# Box_Electronics_v26.net
KiCad netlist of a schematic drawn in EAGLE
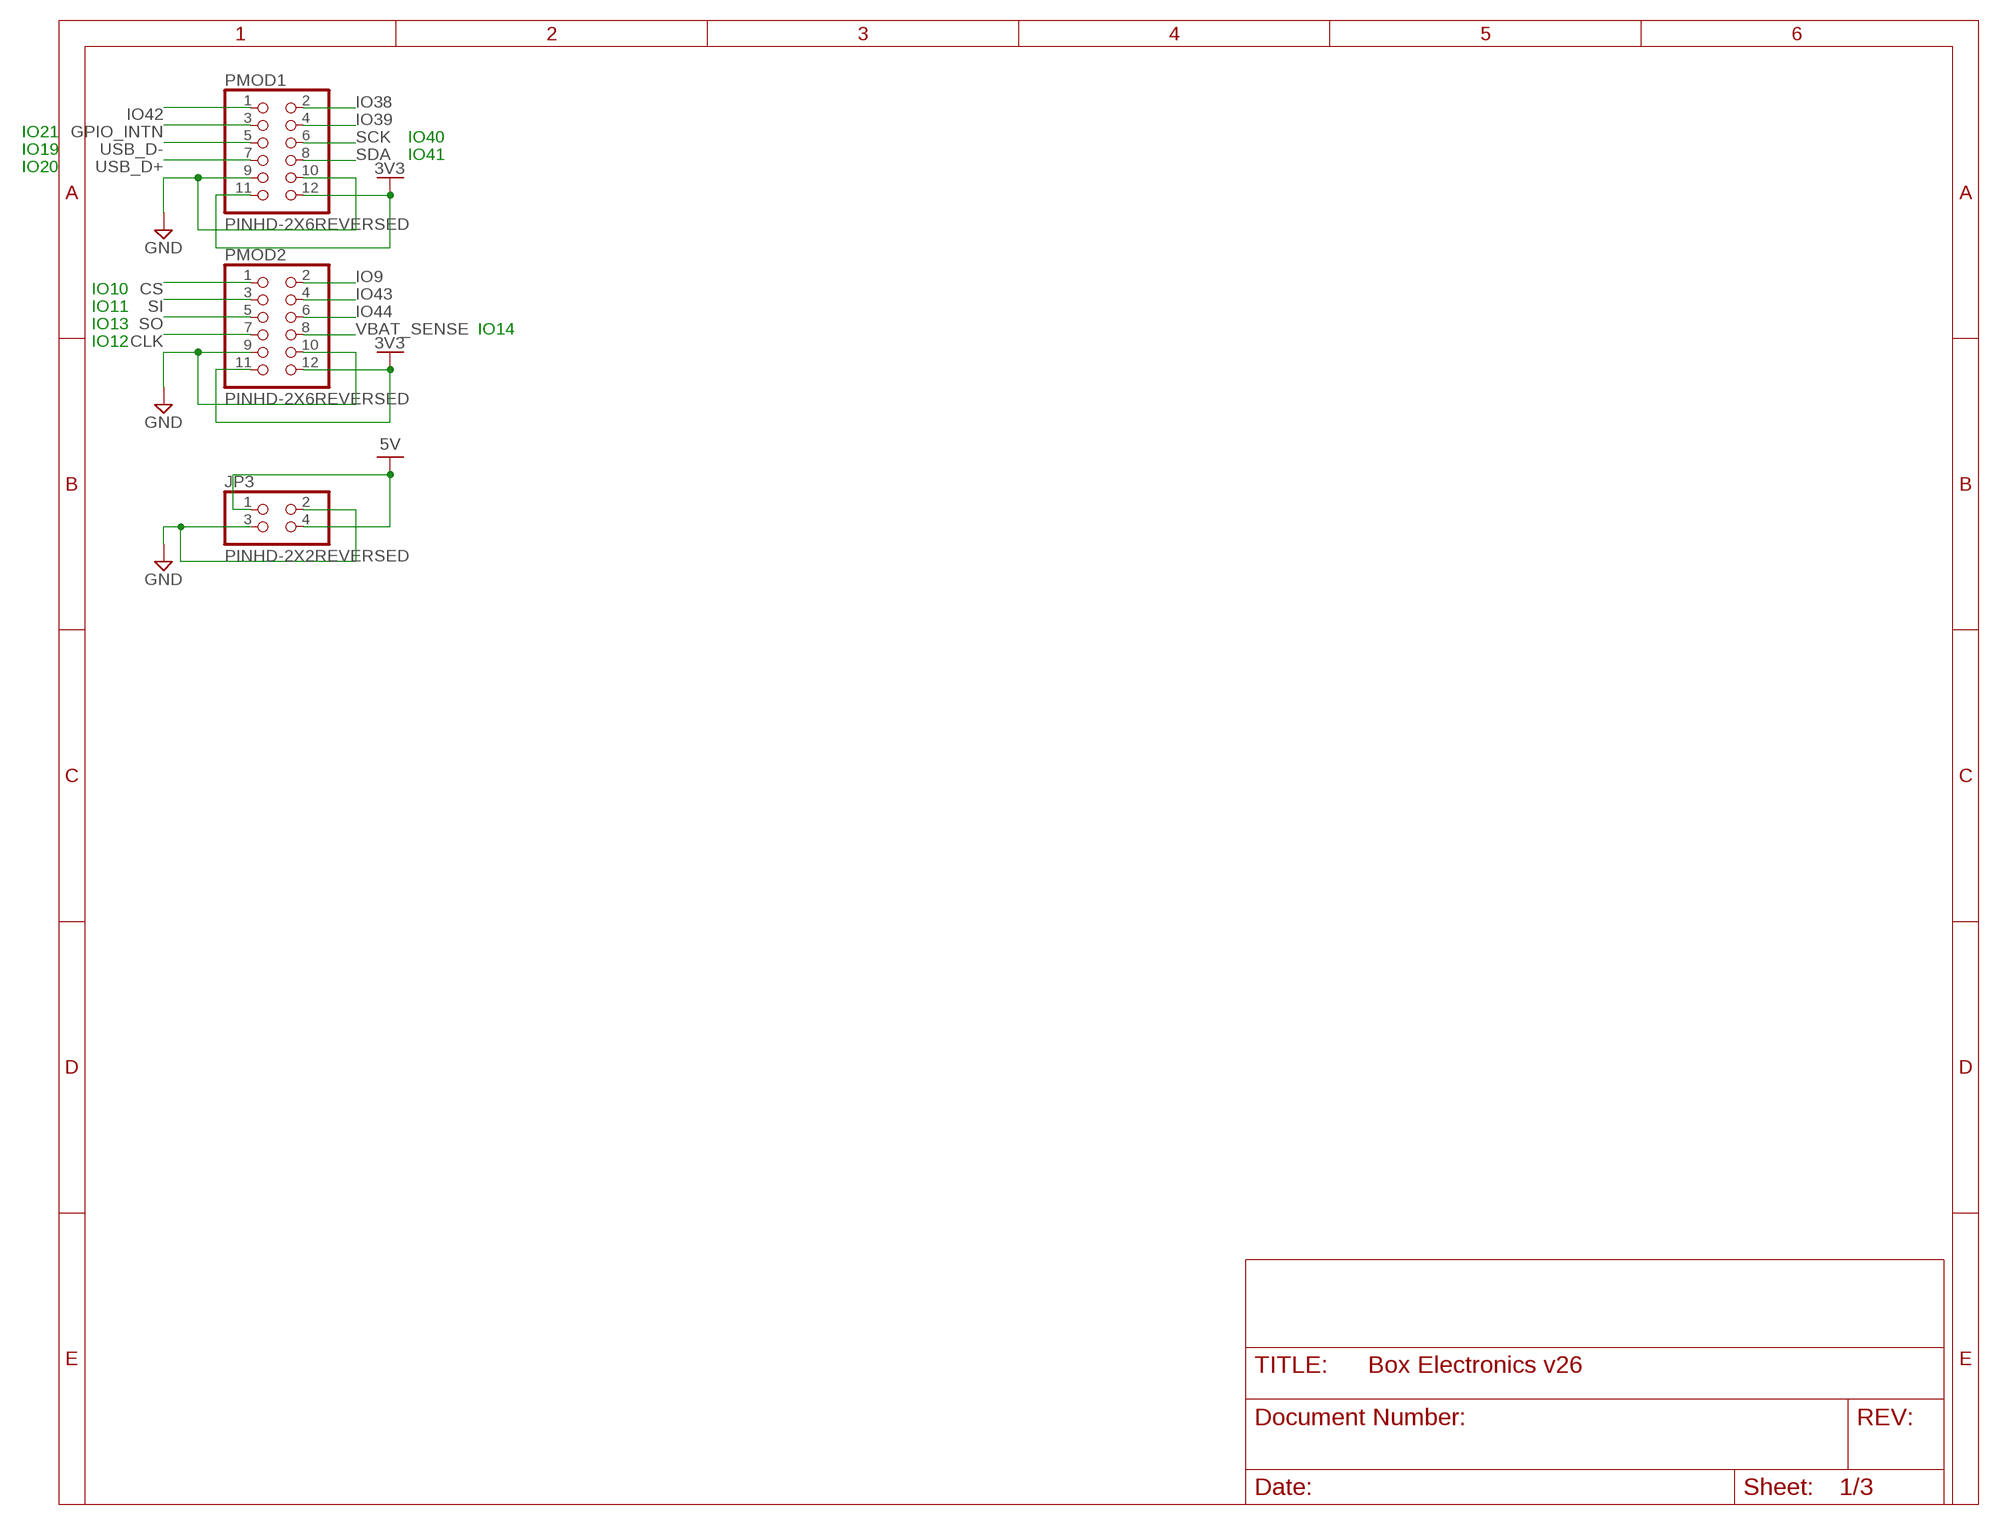
[diagram p0: schematic, sheet 1]
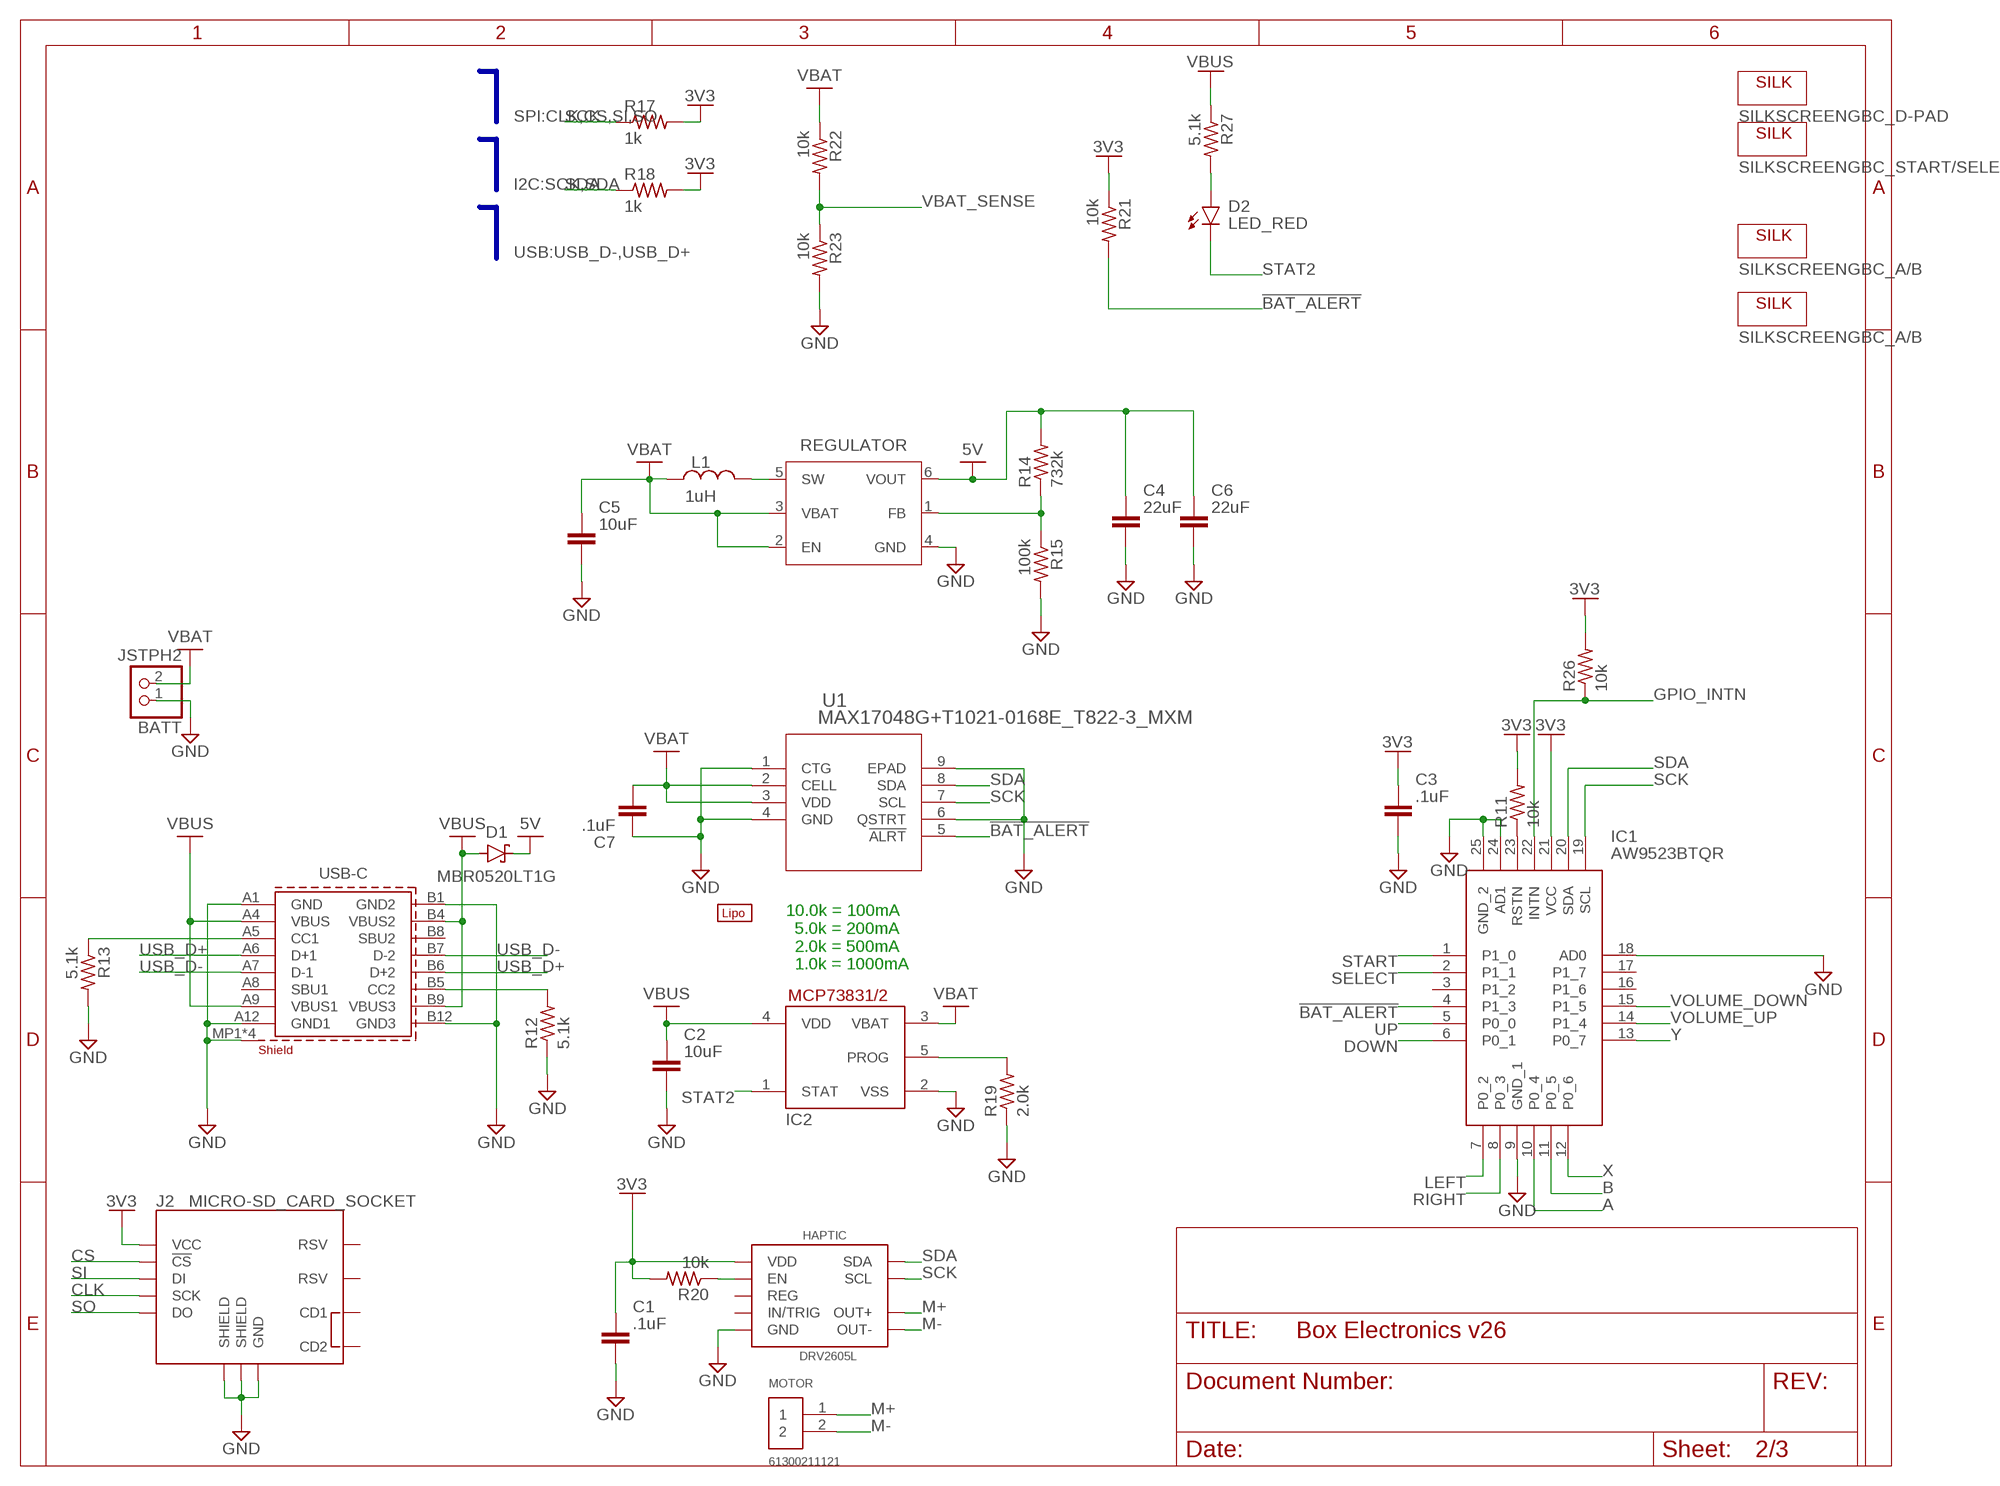
[diagram p1: schematic, sheet 2]
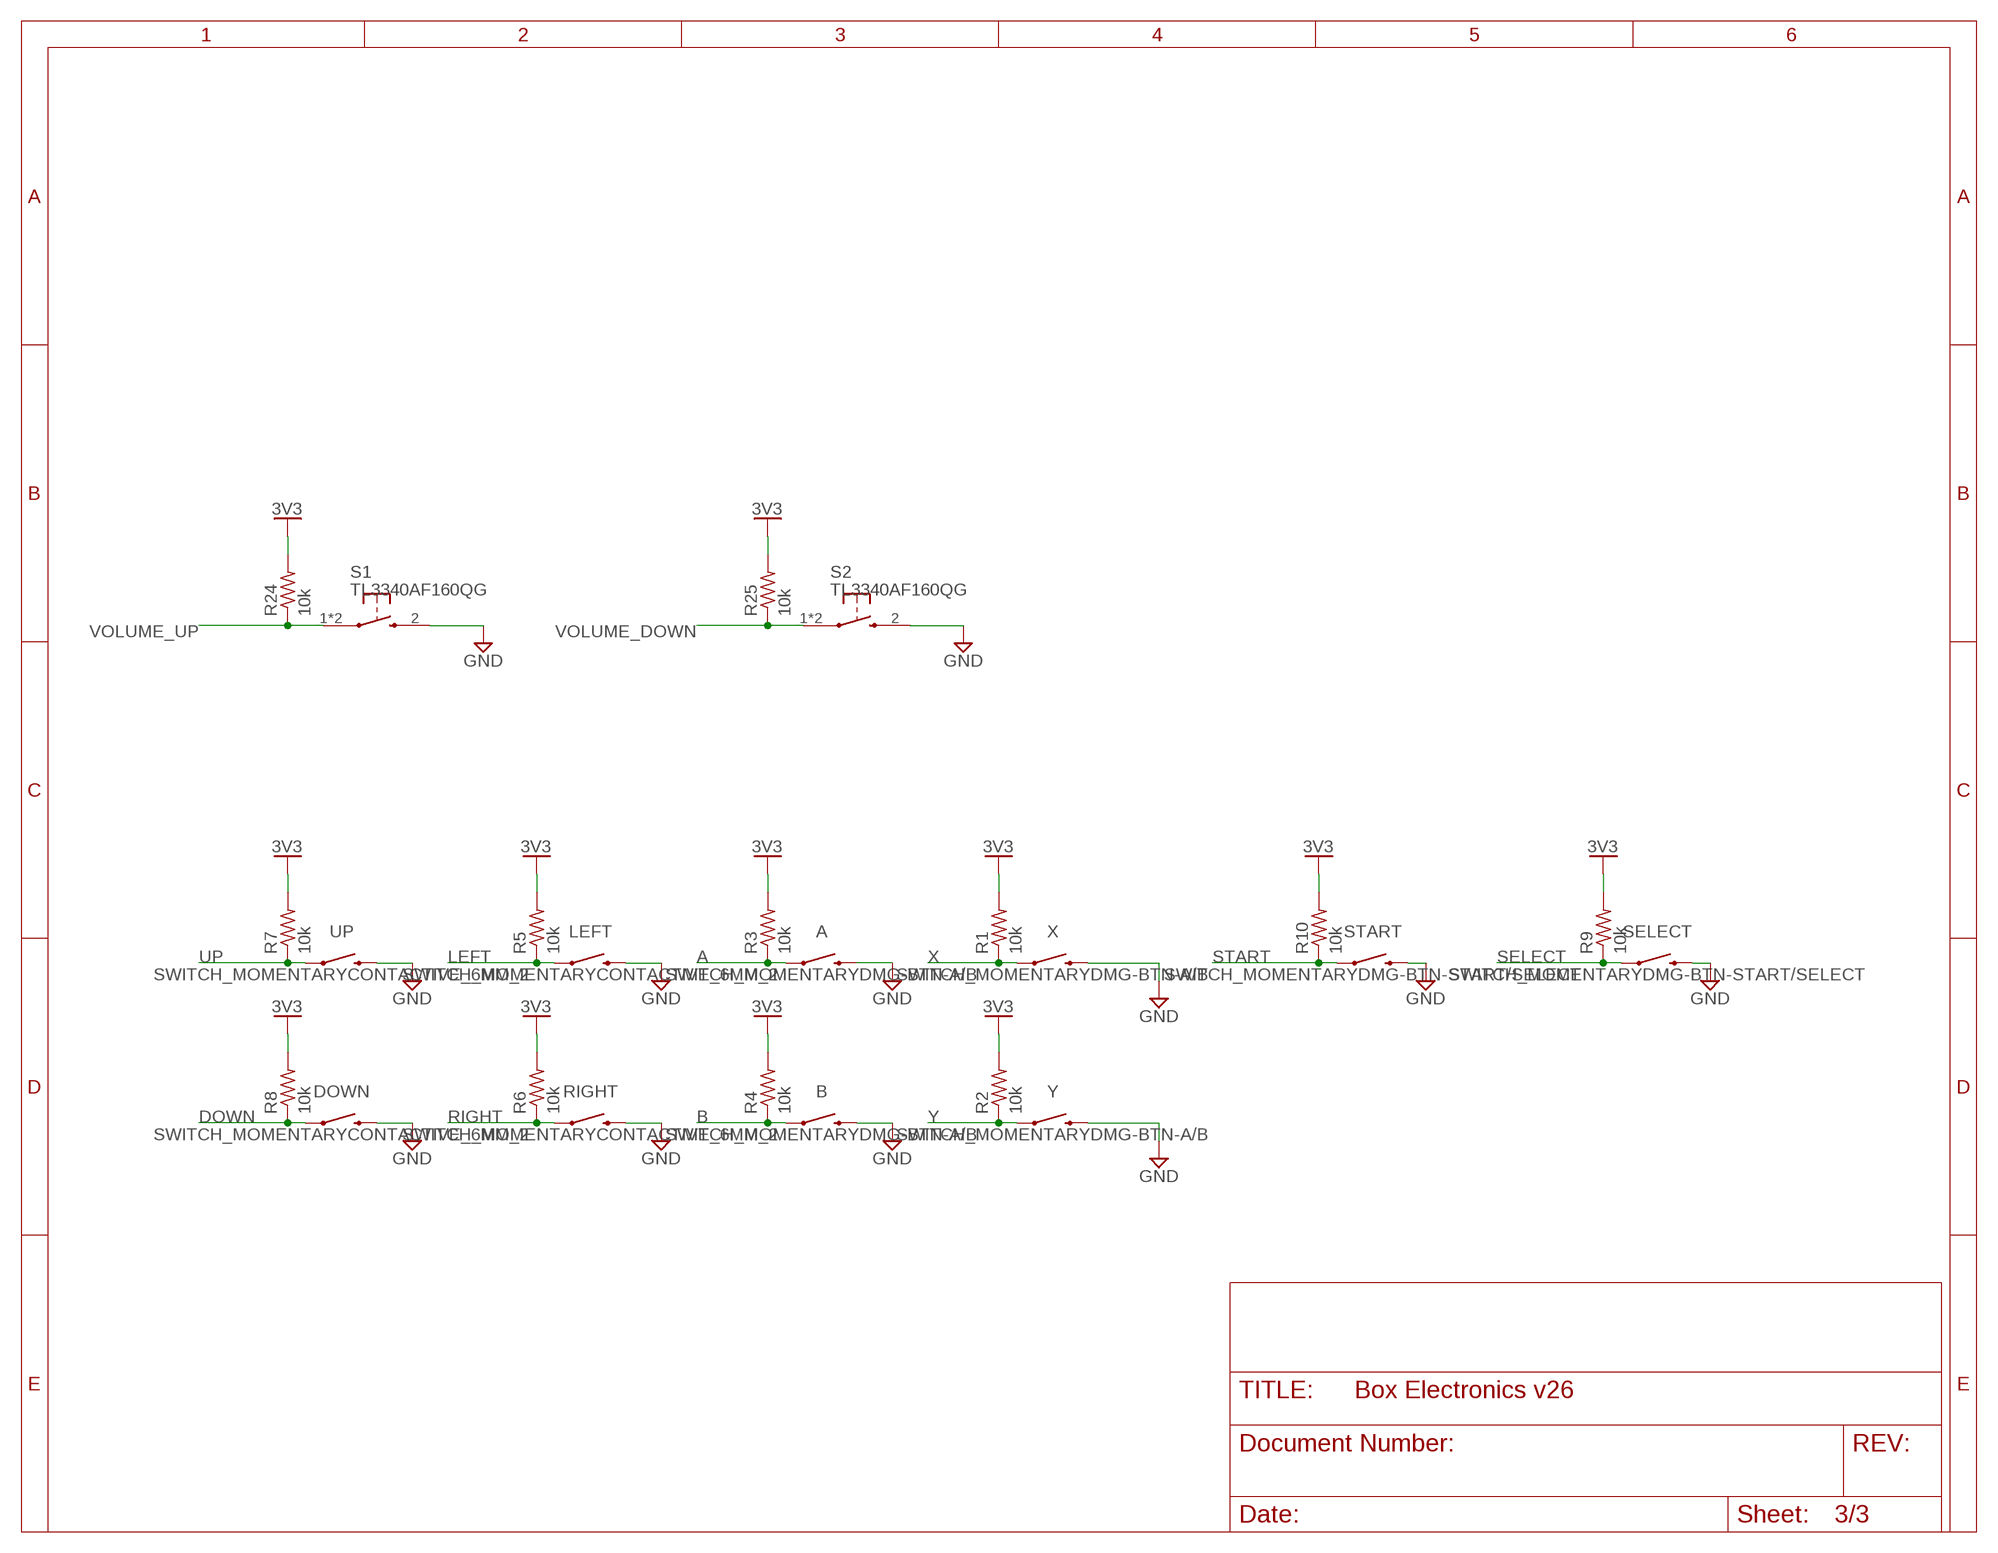
[diagram p2: schematic, sheet 3]

(export (version "E")
  (design (tool "Eeschema 10.0.6"))
  (components
    (comp (ref "BATT")
      (value "JSTPH2")
      (footprint "eagle-import:JSTPH2")
      (libsource (lib "eagle-import") (part "JSTPH2"))
    )
    (comp (ref "BT1")
      (value "LIPO-OUTLINE1100")
      (footprint "eagle-import:LIPO-1000")
      (libsource (lib "eagle-import") (part "LIPO-OUTLINE1100"))
    )
    (comp (ref "C1")
      (value ".1uF")
      (footprint "eagle-import:CAPC1608X85")
      (libsource (lib "eagle-import") (part "CCHIP-0603(1608-METRIC)_"))
    )
    (comp (ref "C2")
      (value "10uF")
      (footprint "eagle-import:CAPC1608X85")
      (libsource (lib "eagle-import") (part "CCHIP-0603(1608-METRIC)_"))
    )
    (comp (ref "C3")
      (value ".1uF")
      (footprint "eagle-import:CAPC1608X85")
      (libsource (lib "eagle-import") (part "CCHIP-0603(1608-METRIC)_"))
    )
    (comp (ref "C4")
      (value "22uF")
      (footprint "eagle-import:CAPC2012X110")
      (libsource (lib "eagle-import") (part "CCHIP-0805(2012-METRIC)_"))
    )
    (comp (ref "C5")
      (value "10uF")
      (footprint "eagle-import:CAPC1608X85")
      (libsource (lib "eagle-import") (part "CCHIP-0603(1608-METRIC)_"))
    )
    (comp (ref "C6")
      (value "22uF")
      (footprint "eagle-import:CAPC2012X110")
      (libsource (lib "eagle-import") (part "CCHIP-0805(2012-METRIC)_"))
    )
    (comp (ref "C7")
      (value ".1uF")
      (footprint "eagle-import:CAPC1608X85")
      (libsource (lib "eagle-import") (part "CCHIP-0603(1608-METRIC)_"))
    )
    (comp (ref "D1")
      (value "MBR0520LT1G")
      (footprint "eagle-import:SODFL3718X115")
      (fields (field (name "MANUFACTURER") "ON Semiconductor"))
      (libsource (lib "eagle-import") (part "SCHOTTKY_DO-219MBR0520LT1G"))
    )
    (comp (ref "D2")
      (value "LED_RED")
      (footprint "eagle-import:LEDC2012X110N_FLAT-R")
      (fields (field (name "MANUFACTURER") "Wurth Electronik") (field (name "MPN") "150080RS75000"))
      (libsource (lib "eagle-import") (part "CHIP-FLAT-R_0805"))
    )
    (comp (ref "HAPTIC")
      (value "DRV2605L")
      (footprint "eagle-import:VSSOP-10")
      (libsource (lib "eagle-import") (part "DRV2605L"))
    )
    (comp (ref "IC1")
      (value "AW9523BTQR")
      (footprint "eagle-import:QFN50P400X400X80-25N")
      (libsource (lib "eagle-import") (part "AW9523BTQR"))
    )
    (comp (ref "IC2")
      (value "MCP73831/OT")
      (footprint "eagle-import:SOT23-5L")
      (libsource (lib "eagle-import") (part "MCP73831/OT"))
    )
    (comp (ref "J2")
      (value "MICRO-SD_CARD_SOCKET")
      (footprint "eagle-import:MICRO-SD-SOCKET")
      (libsource (lib "eagle-import") (part "MICRO-SD_CARD_SOCKET"))
    )
    (comp (ref "L1")
      (value "1uH")
      (footprint "eagle-import:INDC2009X120")
      (libsource (lib "eagle-import") (part "LCHIP-0805(2012-METRIC)_"))
    )
    (comp (ref "MOTOR")
      (value "61300211121")
      (footprint "eagle-import:61300211121")
      (fields
        (field (name "DIGI_KEY_PART_NUMBER") "732-5315-ND")
        (field (name "MANUFACTURER") "Wurth Electronics Inc.")
        (field (name "CREATED_BY") "PCBLayout.com")
      )
      (libsource (lib "eagle-import") (part "61300211121"))
    )
    (comp (ref "R11")
      (value "10k")
      (footprint "eagle-import:RESC1608X60")
      (libsource (lib "eagle-import") (part "R-USCHIP-0603(1608-METRIC)_"))
    )
    (comp (ref "R12")
      (value "5.1k")
      (footprint "eagle-import:RESC1608X60")
      (libsource (lib "eagle-import") (part "R-USCHIP-0603(1608-METRIC)_"))
    )
    (comp (ref "R13")
      (value "5.1k")
      (footprint "eagle-import:RESC1608X60")
      (libsource (lib "eagle-import") (part "R-USCHIP-0603(1608-METRIC)_"))
    )
    (comp (ref "R14")
      (value "732k")
      (footprint "eagle-import:RESC1608X60")
      (libsource (lib "eagle-import") (part "R-USCHIP-0603(1608-METRIC)_"))
    )
    (comp (ref "R15")
      (value "100k")
      (footprint "eagle-import:RESC1608X60")
      (libsource (lib "eagle-import") (part "R-USCHIP-0603(1608-METRIC)_"))
    )
    (comp (ref "R17")
      (value "1k")
      (footprint "eagle-import:RESC1608X60")
      (libsource (lib "eagle-import") (part "R-USCHIP-0603(1608-METRIC)_"))
    )
    (comp (ref "R18")
      (value "1k")
      (footprint "eagle-import:RESC1608X60")
      (libsource (lib "eagle-import") (part "R-USCHIP-0603(1608-METRIC)_"))
    )
    (comp (ref "R19")
      (value "2.0k")
      (footprint "eagle-import:RESC1608X60")
      (libsource (lib "eagle-import") (part "R-USCHIP-0603(1608-METRIC)_"))
    )
    (comp (ref "R20")
      (value "10k")
      (footprint "eagle-import:RESC1608X60")
      (libsource (lib "eagle-import") (part "R-USCHIP-0603(1608-METRIC)_"))
    )
    (comp (ref "R21")
      (value "10k")
      (footprint "eagle-import:RESC1608X60")
      (libsource (lib "eagle-import") (part "R-USCHIP-0603(1608-METRIC)_"))
    )
    (comp (ref "R22")
      (value "10k")
      (footprint "eagle-import:RESC1608X60")
      (libsource (lib "eagle-import") (part "R-USCHIP-0603(1608-METRIC)_"))
    )
    (comp (ref "R23")
      (value "10k")
      (footprint "eagle-import:RESC1608X60")
      (libsource (lib "eagle-import") (part "R-USCHIP-0603(1608-METRIC)_"))
    )
    (comp (ref "R26")
      (value "10k")
      (footprint "eagle-import:RESC1608X60")
      (libsource (lib "eagle-import") (part "R-USCHIP-0603(1608-METRIC)_"))
    )
    (comp (ref "R27")
      (value "5.1k")
      (footprint "eagle-import:RESC1608X60")
      (libsource (lib "eagle-import") (part "R-USCHIP-0603(1608-METRIC)_"))
    )
    (comp (ref "REGULATOR")
      (value "TPS61070")
      (footprint "eagle-import:SOT563")
      (libsource (lib "eagle-import") (part "TPS61023"))
    )
    (comp (ref "U$1")
      (value "SILKSCREENGBC_D-PAD")
      (footprint "eagle-import:GAMEBOY_COLOR_DPAD_SILK")
      (libsource (lib "eagle-import") (part "SILKSCREENGBC_D-PAD"))
    )
    (comp (ref "U$2")
      (value "SILKSCREENGBC_START/SELECT")
      (footprint "eagle-import:GAMEBOY_COLOR_START_SELECT_SILK")
      (libsource (lib "eagle-import") (part "SILKSCREENGBC_START/SELECT"))
    )
    (comp (ref "U$3")
      (value "SILKSCREENGBC_A/B")
      (footprint "eagle-import:GAMEBOY_COLOR_A_B_BUTTON_MEMBRANE")
      (libsource (lib "eagle-import") (part "SILKSCREENGBC_A/B"))
    )
    (comp (ref "U$4")
      (value "SILKSCREENGBC_A/B")
      (footprint "eagle-import:GAMEBOY_COLOR_A_B_BUTTON_MEMBRANE")
      (libsource (lib "eagle-import") (part "SILKSCREENGBC_A/B"))
    )
    (comp (ref "U1")
      (value "MAX17048G+T1021-0168E_T822-3_MXM")
      (footprint "eagle-import:21-0168E_T822-3_MXM")
      (fields
        (field (name "MANUFACTURER_PART_NUMBER") "MAX17048G+T10")
        (field (name "COPYRIGHT") "Copyright (C) 2023 Ultra Librarian. All rights reserved.")
      )
      (libsource (lib "eagle-import") (part "MAX17048G+T1021-0168E_T822-3_MXM"))
    )
    (comp (ref "USB-C")
      (value "629722000214")
      (footprint "eagle-import:USB4110GFA")
      (libsource (lib "eagle-import") (part "629722000214SMD"))
    )
    (comp (ref "JP3")
      (value "PINHD-2X2REVERSED")
      (footprint "eagle-import:2X02_EDGE_REVERSED")
      (libsource (lib "eagle-import") (part "PINHD-2X2REVERSED"))
    )
    (comp (ref "PMOD1")
      (value "PINHD-2X6REVERSED")
      (footprint "eagle-import:2X06_EDGE_REVERSED")
      (libsource (lib "eagle-import") (part "PINHD-2X6REVERSED"))
    )
    (comp (ref "PMOD2")
      (value "PINHD-2X6REVERSED")
      (footprint "eagle-import:2X06_EDGE_REVERSED")
      (libsource (lib "eagle-import") (part "PINHD-2X6REVERSED"))
    )
    (comp (ref "A")
      (value "SWITCH_MOMENTARYDMG-BTN-A/B")
      (footprint "eagle-import:DMG_BTN3")
      (libsource (lib "eagle-import") (part "SWITCH_MOMENTARYDMG-BTN-A/B"))
    )
    (comp (ref "B")
      (value "SWITCH_MOMENTARYDMG-BTN-A/B")
      (footprint "eagle-import:DMG_BTN3")
      (libsource (lib "eagle-import") (part "SWITCH_MOMENTARYDMG-BTN-A/B"))
    )
    (comp (ref "DOWN")
      (value "SWITCH_MOMENTARYCONTACTIVE_6MM_2")
      (footprint "eagle-import:BUTTON-CONDUCTIVE_6MM_2")
      (libsource (lib "eagle-import") (part "SWITCH_MOMENTARYCONTACTIVE_6MM_2"))
    )
    (comp (ref "LEFT")
      (value "SWITCH_MOMENTARYCONTACTIVE_6MM_2")
      (footprint "eagle-import:BUTTON-CONDUCTIVE_6MM_2")
      (libsource (lib "eagle-import") (part "SWITCH_MOMENTARYCONTACTIVE_6MM_2"))
    )
    (comp (ref "R1")
      (value "10k")
      (footprint "eagle-import:RESC1608X60")
      (libsource (lib "eagle-import") (part "R-USCHIP-0603(1608-METRIC)_"))
    )
    (comp (ref "R2")
      (value "10k")
      (footprint "eagle-import:RESC1608X60")
      (libsource (lib "eagle-import") (part "R-USCHIP-0603(1608-METRIC)_"))
    )
    (comp (ref "R3")
      (value "10k")
      (footprint "eagle-import:RESC1608X60")
      (libsource (lib "eagle-import") (part "R-USCHIP-0603(1608-METRIC)_"))
    )
    (comp (ref "R4")
      (value "10k")
      (footprint "eagle-import:RESC1608X60")
      (libsource (lib "eagle-import") (part "R-USCHIP-0603(1608-METRIC)_"))
    )
    (comp (ref "R5")
      (value "10k")
      (footprint "eagle-import:RESC1608X60")
      (libsource (lib "eagle-import") (part "R-USCHIP-0603(1608-METRIC)_"))
    )
    (comp (ref "R6")
      (value "10k")
      (footprint "eagle-import:RESC1608X60")
      (libsource (lib "eagle-import") (part "R-USCHIP-0603(1608-METRIC)_"))
    )
    (comp (ref "R7")
      (value "10k")
      (footprint "eagle-import:RESC1608X60")
      (libsource (lib "eagle-import") (part "R-USCHIP-0603(1608-METRIC)_"))
    )
    (comp (ref "R8")
      (value "10k")
      (footprint "eagle-import:RESC1608X60")
      (libsource (lib "eagle-import") (part "R-USCHIP-0603(1608-METRIC)_"))
    )
    (comp (ref "R9")
      (value "10k")
      (footprint "eagle-import:RESC1608X60")
      (libsource (lib "eagle-import") (part "R-USCHIP-0603(1608-METRIC)_"))
    )
    (comp (ref "R10")
      (value "10k")
      (footprint "eagle-import:RESC1608X60")
      (libsource (lib "eagle-import") (part "R-USCHIP-0603(1608-METRIC)_"))
    )
    (comp (ref "R24")
      (value "10k")
      (footprint "eagle-import:RESC1608X60")
      (libsource (lib "eagle-import") (part "R-USCHIP-0603(1608-METRIC)_"))
    )
    (comp (ref "R25")
      (value "10k")
      (footprint "eagle-import:RESC1608X60")
      (libsource (lib "eagle-import") (part "R-USCHIP-0603(1608-METRIC)_"))
    )
    (comp (ref "RIGHT")
      (value "SWITCH_MOMENTARYCONTACTIVE_6MM_2")
      (footprint "eagle-import:BUTTON-CONDUCTIVE_6MM_2")
      (libsource (lib "eagle-import") (part "SWITCH_MOMENTARYCONTACTIVE_6MM_2"))
    )
    (comp (ref "S1")
      (value "TL3340AF160QG")
      (footprint "eagle-import:TL3340")
      (fields (field (name "MOUSER_PART_NUMBER") "612-TL3340AF160QG"))
      (libsource (lib "eagle-import") (part "TL3340AF160QG"))
    )
    (comp (ref "S2")
      (value "TL3340AF160QG")
      (footprint "eagle-import:TL3340")
      (fields (field (name "MOUSER_PART_NUMBER") "612-TL3340AF160QG"))
      (libsource (lib "eagle-import") (part "TL3340AF160QG"))
    )
    (comp (ref "SELECT")
      (value "SWITCH_MOMENTARYDMG-BTN-START/SELECT")
      (footprint "eagle-import:DMG_BTN1_W2")
      (libsource (lib "eagle-import") (part "SWITCH_MOMENTARYDMG-BTN-START/SELECT"))
    )
    (comp (ref "START")
      (value "SWITCH_MOMENTARYDMG-BTN-START/SELECT")
      (footprint "eagle-import:DMG_BTN1_W2")
      (libsource (lib "eagle-import") (part "SWITCH_MOMENTARYDMG-BTN-START/SELECT"))
    )
    (comp (ref "UP")
      (value "SWITCH_MOMENTARYCONTACTIVE_6MM_2")
      (footprint "eagle-import:BUTTON-CONDUCTIVE_6MM_2")
      (libsource (lib "eagle-import") (part "SWITCH_MOMENTARYCONTACTIVE_6MM_2"))
    )
    (comp (ref "X")
      (value "SWITCH_MOMENTARYDMG-BTN-A/B")
      (footprint "eagle-import:DMG_BTN3")
      (libsource (lib "eagle-import") (part "SWITCH_MOMENTARYDMG-BTN-A/B"))
    )
    (comp (ref "Y")
      (value "SWITCH_MOMENTARYDMG-BTN-A/B")
      (footprint "eagle-import:DMG_BTN3")
      (libsource (lib "eagle-import") (part "SWITCH_MOMENTARYDMG-BTN-A/B"))
    )
  )
  (nets
    (net (code "7") (name "3V3") (class "Default")
      (node (ref "C1") (pin "1") (pinfunction "1_1") (pintype "passive"))
      (node (ref "C3") (pin "1") (pinfunction "1_1") (pintype "passive"))
      (node (ref "HAPTIC") (pin "10") (pinfunction "VDD_10") (pintype "bidirectional"))
      (node (ref "HAPTIC") (pin "6") (pinfunction "VDD_6") (pintype "bidirectional"))
      (node (ref "IC1") (pin "21") (pinfunction "VCC_21") (pintype "bidirectional"))
      (node (ref "J2") (pin "VCC") (pinfunction "VCC_VCC") (pintype "bidirectional"))
      (node (ref "PMOD1") (pin "11") (pinfunction "11_11") (pintype "passive"))
      (node (ref "PMOD1") (pin "12") (pinfunction "12_12") (pintype "passive"))
      (node (ref "PMOD2") (pin "11") (pinfunction "11_11") (pintype "passive"))
      (node (ref "PMOD2") (pin "12") (pinfunction "12_12") (pintype "passive"))
      (node (ref "R1") (pin "2") (pinfunction "2_2") (pintype "passive"))
      (node (ref "R10") (pin "2") (pinfunction "2_2") (pintype "passive"))
      (node (ref "R11") (pin "2") (pinfunction "2_2") (pintype "passive"))
      (node (ref "R17") (pin "2") (pinfunction "2_2") (pintype "passive"))
      (node (ref "R18") (pin "2") (pinfunction "2_2") (pintype "passive"))
      (node (ref "R2") (pin "2") (pinfunction "2_2") (pintype "passive"))
      (node (ref "R20") (pin "2") (pinfunction "2_2") (pintype "passive"))
      (node (ref "R21") (pin "1") (pinfunction "1_1") (pintype "passive"))
      (node (ref "R24") (pin "2") (pinfunction "2_2") (pintype "passive"))
      (node (ref "R25") (pin "2") (pinfunction "2_2") (pintype "passive"))
      (node (ref "R26") (pin "2") (pinfunction "2_2") (pintype "passive"))
      (node (ref "R3") (pin "2") (pinfunction "2_2") (pintype "passive"))
      (node (ref "R4") (pin "2") (pinfunction "2_2") (pintype "passive"))
      (node (ref "R5") (pin "2") (pinfunction "2_2") (pintype "passive"))
      (node (ref "R6") (pin "2") (pinfunction "2_2") (pintype "passive"))
      (node (ref "R7") (pin "2") (pinfunction "2_2") (pintype "passive"))
      (node (ref "R8") (pin "2") (pinfunction "2_2") (pintype "passive"))
      (node (ref "R9") (pin "2") (pinfunction "2_2") (pintype "passive"))
    )
    (net (code "8") (name "5V") (class "Default")
      (node (ref "C4") (pin "1") (pinfunction "1_1") (pintype "passive"))
      (node (ref "C6") (pin "1") (pinfunction "1_1") (pintype "passive"))
      (node (ref "D1") (pin "1") (pinfunction "C_1") (pintype "passive"))
      (node (ref "JP3") (pin "1") (pinfunction "1_1") (pintype "passive"))
      (node (ref "JP3") (pin "4") (pinfunction "4_4") (pintype "passive"))
      (node (ref "R14") (pin "2") (pinfunction "2_2") (pintype "passive"))
      (node (ref "REGULATOR") (pin "6") (pinfunction "VOUT_6") (pintype "output"))
    )
    (net (code "9") (name "A") (class "Default")
      (node (ref "A") (pin "P$1") (pinfunction "1_P$1") (pintype "passive"))
      (node (ref "A") (pin "P$3") (pinfunction "1_P$3") (pintype "passive"))
      (node (ref "IC1") (pin "10") (pinfunction "P0_4_10") (pintype "bidirectional"))
      (node (ref "R3") (pin "1") (pinfunction "1_1") (pintype "passive"))
    )
    (net (code "10") (name "B") (class "Default")
      (node (ref "B") (pin "P$1") (pinfunction "1_P$1") (pintype "passive"))
      (node (ref "B") (pin "P$3") (pinfunction "1_P$3") (pintype "passive"))
      (node (ref "IC1") (pin "11") (pinfunction "P0_5_11") (pintype "bidirectional"))
      (node (ref "R4") (pin "1") (pinfunction "1_1") (pintype "passive"))
    )
    (net (code "11") (name "CLK") (class "Default")
      (node (ref "J2") (pin "SCLK") (pinfunction "SCK_SCLK") (pintype "bidirectional"))
      (node (ref "PMOD2") (pin "7") (pinfunction "7_7") (pintype "passive"))
    )
    (net (code "12") (name "CS") (class "Default")
      (node (ref "J2") (pin "CS") (pinfunction "~{CS}_CS") (pintype "bidirectional"))
      (node (ref "PMOD2") (pin "1") (pinfunction "1_1") (pintype "passive"))
    )
    (net (code "13") (name "DOWN") (class "Default")
      (node (ref "DOWN") (pin "1") (pinfunction "1_1") (pintype "passive"))
      (node (ref "IC1") (pin "6") (pinfunction "P0_1_6") (pintype "bidirectional"))
      (node (ref "R8") (pin "1") (pinfunction "1_1") (pintype "passive"))
    )
    (net (code "14") (name "GND") (class "Default")
      (node (ref "A") (pin "P$2") (pinfunction "2_P$2") (pintype "passive"))
      (node (ref "A") (pin "P$4") (pinfunction "2_P$4") (pintype "passive"))
      (node (ref "B") (pin "P$2") (pinfunction "2_P$2") (pintype "passive"))
      (node (ref "B") (pin "P$4") (pinfunction "2_P$4") (pintype "passive"))
      (node (ref "BATT") (pin "1") (pinfunction "1_1") (pintype "passive"))
      (node (ref "C1") (pin "2") (pinfunction "2_2") (pintype "passive"))
      (node (ref "C2") (pin "2") (pinfunction "2_2") (pintype "passive"))
      (node (ref "C3") (pin "2") (pinfunction "2_2") (pintype "passive"))
      (node (ref "C4") (pin "2") (pinfunction "2_2") (pintype "passive"))
      (node (ref "C5") (pin "2") (pinfunction "2_2") (pintype "passive"))
      (node (ref "C6") (pin "2") (pinfunction "2_2") (pintype "passive"))
      (node (ref "C7") (pin "1") (pinfunction "1_1") (pintype "passive"))
      (node (ref "DOWN") (pin "2") (pinfunction "2_2") (pintype "passive"))
      (node (ref "HAPTIC") (pin "8") (pinfunction "GND_8") (pintype "bidirectional"))
      (node (ref "IC1") (pin "18") (pinfunction "AD0_18") (pintype "bidirectional"))
      (node (ref "IC1") (pin "24") (pinfunction "AD1_24") (pintype "bidirectional"))
      (node (ref "IC1") (pin "25") (pinfunction "GND_2_25") (pintype "bidirectional"))
      (node (ref "IC1") (pin "9") (pinfunction "GND_1_9") (pintype "bidirectional"))
      (node (ref "IC2") (pin "2") (pinfunction "VSS_2") (pintype "power_in"))
      (node (ref "J2") (pin "GND") (pinfunction "GND_GND") (pintype "bidirectional"))
      (node (ref "J2") (pin "GND1") (pinfunction "SHIELD_GND1") (pintype "bidirectional"))
      (node (ref "J2") (pin "GND3") (pinfunction "SHIELD_GND3") (pintype "bidirectional"))
      (node (ref "JP3") (pin "2") (pinfunction "2_2") (pintype "passive"))
      (node (ref "JP3") (pin "3") (pinfunction "3_3") (pintype "passive"))
      (node (ref "LEFT") (pin "2") (pinfunction "2_2") (pintype "passive"))
      (node (ref "PMOD1") (pin "10") (pinfunction "10_10") (pintype "passive"))
      (node (ref "PMOD1") (pin "9") (pinfunction "9_9") (pintype "passive"))
      (node (ref "PMOD2") (pin "10") (pinfunction "10_10") (pintype "passive"))
      (node (ref "PMOD2") (pin "9") (pinfunction "9_9") (pintype "passive"))
      (node (ref "R12") (pin "1") (pinfunction "1_1") (pintype "passive"))
      (node (ref "R13") (pin "2") (pinfunction "2_2") (pintype "passive"))
      (node (ref "R15") (pin "2") (pinfunction "2_2") (pintype "passive"))
      (node (ref "R19") (pin "1") (pinfunction "1_1") (pintype "passive"))
      (node (ref "R23") (pin "2") (pinfunction "2_2") (pintype "passive"))
      (node (ref "REGULATOR") (pin "4") (pinfunction "GND_4") (pintype "power_in"))
      (node (ref "RIGHT") (pin "2") (pinfunction "2_2") (pintype "passive"))
      (node (ref "S1") (pin "2") (pinfunction "2_2") (pintype "bidirectional"))
      (node (ref "S2") (pin "2") (pinfunction "2_2") (pintype "bidirectional"))
      (node (ref "SELECT") (pin "P$2") (pinfunction "2_P$2") (pintype "passive"))
      (node (ref "SELECT") (pin "P$4") (pinfunction "2_P$4") (pintype "passive"))
      (node (ref "START") (pin "P$2") (pinfunction "2_P$2") (pintype "passive"))
      (node (ref "START") (pin "P$4") (pinfunction "2_P$4") (pintype "passive"))
      (node (ref "U1") (pin "1") (pinfunction "CTG_1") (pintype "passive"))
      (node (ref "U1") (pin "4") (pinfunction "GND_4") (pintype "power_in"))
      (node (ref "U1") (pin "6") (pinfunction "QSTRT_6") (pintype "input"))
      (node (ref "U1") (pin "9") (pinfunction "EPAD_9") (pintype "passive"))
      (node (ref "UP") (pin "2") (pinfunction "2_2") (pintype "passive"))
      (node (ref "USB-C") (pin "A1") (pinfunction "GND_A1") (pintype "passive"))
      (node (ref "USB-C") (pin "A12") (pinfunction "GND1_A12") (pintype "passive"))
      (node (ref "USB-C") (pin "B1") (pinfunction "GND2_B1") (pintype "passive"))
      (node (ref "USB-C") (pin "B12") (pinfunction "GND3_B12") (pintype "passive"))
      (node (ref "USB-C") (pin "MP1") (pinfunction "SHIELD_MP1") (pintype "passive"))
      (node (ref "USB-C") (pin "MP2") (pinfunction "SHIELD_MP2") (pintype "passive"))
      (node (ref "USB-C") (pin "MP3") (pinfunction "SHIELD_MP3") (pintype "passive"))
      (node (ref "USB-C") (pin "MP4") (pinfunction "SHIELD_MP4") (pintype "passive"))
      (node (ref "X") (pin "P$2") (pinfunction "2_P$2") (pintype "passive"))
      (node (ref "X") (pin "P$4") (pinfunction "2_P$4") (pintype "passive"))
      (node (ref "Y") (pin "P$2") (pinfunction "2_P$2") (pintype "passive"))
      (node (ref "Y") (pin "P$4") (pinfunction "2_P$4") (pintype "passive"))
    )
    (net (code "15") (name "GPIO_INTN") (class "Default")
      (node (ref "IC1") (pin "22") (pinfunction "INTN_22") (pintype "bidirectional"))
      (node (ref "PMOD1") (pin "3") (pinfunction "3_3") (pintype "passive"))
      (node (ref "R26") (pin "1") (pinfunction "1_1") (pintype "passive"))
    )
    (net (code "16") (name "IO9") (class "Default")
      (node (ref "PMOD2") (pin "2") (pinfunction "2_2") (pintype "passive"))
    )
    (net (code "17") (name "IO38") (class "Default")
      (node (ref "PMOD1") (pin "2") (pinfunction "2_2") (pintype "passive"))
    )
    (net (code "18") (name "IO39") (class "Default")
      (node (ref "PMOD1") (pin "4") (pinfunction "4_4") (pintype "passive"))
    )
    (net (code "19") (name "IO42") (class "Default")
      (node (ref "PMOD1") (pin "1") (pinfunction "1_1") (pintype "passive"))
    )
    (net (code "20") (name "IO43") (class "Default")
      (node (ref "PMOD2") (pin "4") (pinfunction "4_4") (pintype "passive"))
    )
    (net (code "21") (name "IO44") (class "Default")
      (node (ref "PMOD2") (pin "6") (pinfunction "6_6") (pintype "passive"))
    )
    (net (code "22") (name "LEFT") (class "Default")
      (node (ref "IC1") (pin "7") (pinfunction "P0_2_7") (pintype "bidirectional"))
      (node (ref "LEFT") (pin "1") (pinfunction "1_1") (pintype "passive"))
      (node (ref "R5") (pin "1") (pinfunction "1_1") (pintype "passive"))
    )
    (net (code "23") (name "M+") (class "Default")
      (node (ref "HAPTIC") (pin "7") (pinfunction "OUT+_7") (pintype "bidirectional"))
      (node (ref "MOTOR") (pin "1") (pinfunction "1_1") (pintype "passive"))
    )
    (net (code "24") (name "M-") (class "Default")
      (node (ref "HAPTIC") (pin "9") (pinfunction "OUT-_9") (pintype "bidirectional"))
      (node (ref "MOTOR") (pin "2") (pinfunction "2_2") (pintype "passive"))
    )
    (net (code "25") (name "Net-(D2-PadA)") (class "Default")
      (node (ref "D2") (pin "A") (pinfunction "A_A") (pintype "passive"))
      (node (ref "R27") (pin "2") (pinfunction "2_2") (pintype "passive"))
    )
    (net (code "26") (name "Net-(HAPTIC-EN)") (class "Default")
      (node (ref "HAPTIC") (pin "5") (pinfunction "EN_5") (pintype "bidirectional"))
      (node (ref "R20") (pin "1") (pinfunction "1_1") (pintype "passive"))
    )
    (net (code "27") (name "Net-(IC1-RSTN)") (class "Default")
      (node (ref "IC1") (pin "23") (pinfunction "RSTN_23") (pintype "bidirectional"))
      (node (ref "R11") (pin "1") (pinfunction "1_1") (pintype "passive"))
    )
    (net (code "28") (name "Net-(IC2-PROG)") (class "Default")
      (node (ref "IC2") (pin "5") (pinfunction "PROG_5") (pintype "input"))
      (node (ref "R19") (pin "2") (pinfunction "2_2") (pintype "passive"))
    )
    (net (code "29") (name "Net-(REGULATOR-FB)") (class "Default")
      (node (ref "R14") (pin "1") (pinfunction "1_1") (pintype "passive"))
      (node (ref "R15") (pin "1") (pinfunction "1_1") (pintype "passive"))
      (node (ref "REGULATOR") (pin "1") (pinfunction "FB_1") (pintype "input"))
    )
    (net (code "30") (name "Net-(REGULATOR-SW)") (class "Default")
      (node (ref "L1") (pin "2") (pinfunction "2_2") (pintype "passive"))
      (node (ref "REGULATOR") (pin "5") (pinfunction "SW_5") (pintype "input"))
    )
    (net (code "31") (name "Net-(USB-C-CC1)") (class "Default")
      (node (ref "R13") (pin "1") (pinfunction "1_1") (pintype "passive"))
      (node (ref "USB-C") (pin "A5") (pinfunction "CC1_A5") (pintype "passive"))
    )
    (net (code "32") (name "Net-(USB-C-CC2)") (class "Default")
      (node (ref "R12") (pin "2") (pinfunction "2_2") (pintype "passive"))
      (node (ref "USB-C") (pin "B5") (pinfunction "CC2_B5") (pintype "passive"))
    )
    (net (code "33") (name "RIGHT") (class "Default")
      (node (ref "IC1") (pin "8") (pinfunction "P0_3_8") (pintype "bidirectional"))
      (node (ref "R6") (pin "1") (pinfunction "1_1") (pintype "passive"))
      (node (ref "RIGHT") (pin "1") (pinfunction "1_1") (pintype "passive"))
    )
    (net (code "34") (name "SCK") (class "Default")
      (node (ref "HAPTIC") (pin "2") (pinfunction "SCL_2") (pintype "bidirectional"))
      (node (ref "IC1") (pin "19") (pinfunction "SCL_19") (pintype "bidirectional"))
      (node (ref "PMOD1") (pin "6") (pinfunction "6_6") (pintype "passive"))
      (node (ref "R17") (pin "1") (pinfunction "1_1") (pintype "passive"))
      (node (ref "U1") (pin "7") (pinfunction "SCL_7") (pintype "input"))
    )
    (net (code "35") (name "SDA") (class "Default")
      (node (ref "HAPTIC") (pin "3") (pinfunction "SDA_3") (pintype "bidirectional"))
      (node (ref "IC1") (pin "20") (pinfunction "SDA_20") (pintype "bidirectional"))
      (node (ref "PMOD1") (pin "8") (pinfunction "8_8") (pintype "passive"))
      (node (ref "R18") (pin "1") (pinfunction "1_1") (pintype "passive"))
      (node (ref "U1") (pin "8") (pinfunction "SDA_8") (pintype "bidirectional"))
    )
    (net (code "36") (name "SELECT") (class "Default")
      (node (ref "IC1") (pin "2") (pinfunction "P1_1_2") (pintype "bidirectional"))
      (node (ref "R9") (pin "1") (pinfunction "1_1") (pintype "passive"))
      (node (ref "SELECT") (pin "P$1") (pinfunction "1_P$1") (pintype "passive"))
      (node (ref "SELECT") (pin "P$3") (pinfunction "1_P$3") (pintype "passive"))
    )
    (net (code "37") (name "SI") (class "Default")
      (node (ref "J2") (pin "DI") (pinfunction "DI_DI") (pintype "bidirectional"))
      (node (ref "PMOD2") (pin "3") (pinfunction "3_3") (pintype "passive"))
    )
    (net (code "38") (name "SO") (class "Default")
      (node (ref "J2") (pin "DO") (pinfunction "DO_DO") (pintype "bidirectional"))
      (node (ref "PMOD2") (pin "5") (pinfunction "5_5") (pintype "passive"))
    )
    (net (code "39") (name "START") (class "Default")
      (node (ref "IC1") (pin "1") (pinfunction "P1_0_1") (pintype "bidirectional"))
      (node (ref "R10") (pin "1") (pinfunction "1_1") (pintype "passive"))
      (node (ref "START") (pin "P$1") (pinfunction "1_P$1") (pintype "passive"))
      (node (ref "START") (pin "P$3") (pinfunction "1_P$3") (pintype "passive"))
    )
    (net (code "40") (name "STAT2") (class "Default")
      (node (ref "D2") (pin "C") (pinfunction "C_C") (pintype "passive"))
      (node (ref "IC2") (pin "1") (pinfunction "STAT_1") (pintype "output"))
    )
    (net (code "41") (name "UP") (class "Default")
      (node (ref "IC1") (pin "5") (pinfunction "P0_0_5") (pintype "bidirectional"))
      (node (ref "R7") (pin "1") (pinfunction "1_1") (pintype "passive"))
      (node (ref "UP") (pin "1") (pinfunction "1_1") (pintype "passive"))
    )
    (net (code "42") (name "USB_D+") (class "Default")
      (node (ref "PMOD1") (pin "7") (pinfunction "7_7") (pintype "passive"))
      (node (ref "USB-C") (pin "A6") (pinfunction "D+1_A6") (pintype "passive"))
      (node (ref "USB-C") (pin "B6") (pinfunction "D+2_B6") (pintype "passive"))
    )
    (net (code "43") (name "USB_D-") (class "Default")
      (node (ref "PMOD1") (pin "5") (pinfunction "5_5") (pintype "passive"))
      (node (ref "USB-C") (pin "A7") (pinfunction "D-1_A7") (pintype "passive"))
      (node (ref "USB-C") (pin "B7") (pinfunction "D-2_B7") (pintype "passive"))
    )
    (net (code "44") (name "VBAT") (class "Default")
      (node (ref "BATT") (pin "2") (pinfunction "2_2") (pintype "passive"))
      (node (ref "C5") (pin "1") (pinfunction "1_1") (pintype "passive"))
      (node (ref "C7") (pin "2") (pinfunction "2_2") (pintype "passive"))
      (node (ref "IC2") (pin "3") (pinfunction "VBAT_3") (pintype "bidirectional"))
      (node (ref "L1") (pin "1") (pinfunction "1_1") (pintype "passive"))
      (node (ref "R22") (pin "1") (pinfunction "1_1") (pintype "passive"))
      (node (ref "REGULATOR") (pin "2") (pinfunction "EN_2") (pintype "input"))
      (node (ref "REGULATOR") (pin "3") (pinfunction "VBAT_3") (pintype "input"))
      (node (ref "U1") (pin "2") (pinfunction "CELL_2") (pintype "passive"))
      (node (ref "U1") (pin "3") (pinfunction "VDD_3") (pintype "power_in"))
    )
    (net (code "45") (name "VBAT_SENSE") (class "Default")
      (node (ref "PMOD2") (pin "8") (pinfunction "8_8") (pintype "passive"))
      (node (ref "R22") (pin "2") (pinfunction "2_2") (pintype "passive"))
      (node (ref "R23") (pin "1") (pinfunction "1_1") (pintype "passive"))
    )
    (net (code "46") (name "VBUS") (class "Default")
      (node (ref "C2") (pin "1") (pinfunction "1_1") (pintype "passive"))
      (node (ref "D1") (pin "2") (pinfunction "A_2") (pintype "passive"))
      (node (ref "IC2") (pin "4") (pinfunction "VDD_4") (pintype "power_in"))
      (node (ref "R27") (pin "1") (pinfunction "1_1") (pintype "passive"))
      (node (ref "USB-C") (pin "A4") (pinfunction "VBUS_A4") (pintype "passive"))
      (node (ref "USB-C") (pin "A9") (pinfunction "VBUS1_A9") (pintype "passive"))
      (node (ref "USB-C") (pin "B4") (pinfunction "VBUS2_B4") (pintype "passive"))
      (node (ref "USB-C") (pin "B9") (pinfunction "VBUS3_B9") (pintype "passive"))
    )
    (net (code "47") (name "VOLUME_DOWN") (class "Default")
      (node (ref "IC1") (pin "15") (pinfunction "P1_5_15") (pintype "bidirectional"))
      (node (ref "R25") (pin "1") (pinfunction "1_1") (pintype "passive"))
      (node (ref "S2") (pin "1") (pinfunction "1_1") (pintype "bidirectional"))
      (node (ref "S2") (pin "3") (pinfunction "1_3") (pintype "bidirectional"))
    )
    (net (code "48") (name "VOLUME_UP") (class "Default")
      (node (ref "IC1") (pin "14") (pinfunction "P1_4_14") (pintype "bidirectional"))
      (node (ref "R24") (pin "1") (pinfunction "1_1") (pintype "passive"))
      (node (ref "S1") (pin "1") (pinfunction "1_1") (pintype "bidirectional"))
      (node (ref "S1") (pin "3") (pinfunction "1_3") (pintype "bidirectional"))
    )
    (net (code "49") (name "X") (class "Default")
      (node (ref "IC1") (pin "12") (pinfunction "P0_6_12") (pintype "bidirectional"))
      (node (ref "R1") (pin "1") (pinfunction "1_1") (pintype "passive"))
      (node (ref "X") (pin "P$1") (pinfunction "1_P$1") (pintype "passive"))
      (node (ref "X") (pin "P$3") (pinfunction "1_P$3") (pintype "passive"))
    )
    (net (code "50") (name "Y") (class "Default")
      (node (ref "IC1") (pin "13") (pinfunction "P0_7_13") (pintype "bidirectional"))
      (node (ref "R2") (pin "1") (pinfunction "1_1") (pintype "passive"))
      (node (ref "Y") (pin "P$1") (pinfunction "1_P$1") (pintype "passive"))
      (node (ref "Y") (pin "P$3") (pinfunction "1_P$3") (pintype "passive"))
    )
    (net (code "51") (name "unconnected-(HAPTIC-IN{slash}TRIG-Pad4)") (class "Default")
      (node (ref "HAPTIC") (pin "4") (pinfunction "IN/TRIG_4") (pintype "bidirectional"))
    )
    (net (code "52") (name "unconnected-(HAPTIC-REG-Pad1)") (class "Default")
      (node (ref "HAPTIC") (pin "1") (pinfunction "REG_1") (pintype "bidirectional"))
    )
    (net (code "53") (name "unconnected-(IC1-P1_2-Pad3)") (class "Default")
      (node (ref "IC1") (pin "3") (pinfunction "P1_2_3") (pintype "bidirectional"))
    )
    (net (code "54") (name "unconnected-(IC1-P1_6-Pad16)") (class "Default")
      (node (ref "IC1") (pin "16") (pinfunction "P1_6_16") (pintype "bidirectional"))
    )
    (net (code "55") (name "unconnected-(IC1-P1_7-Pad17)") (class "Default")
      (node (ref "IC1") (pin "17") (pinfunction "P1_7_17") (pintype "bidirectional"))
    )
    (net (code "56") (name "unconnected-(J2-PadCD1)") (class "Default")
      (node (ref "J2") (pin "CD1") (pinfunction "CD1_CD1") (pintype "bidirectional"))
    )
    (net (code "57") (name "unconnected-(J2-PadCD2)") (class "Default")
      (node (ref "J2") (pin "CD2") (pinfunction "CD2_CD2") (pintype "bidirectional"))
    )
    (net (code "58") (name "unconnected-(J2-RSV-PadRSV1)") (class "Default")
      (node (ref "J2") (pin "RSV1") (pinfunction "RSV_RSV1") (pintype "bidirectional"))
    )
    (net (code "59") (name "unconnected-(J2-RSV-PadRSV2)") (class "Default")
      (node (ref "J2") (pin "RSV2") (pinfunction "RSV_RSV2") (pintype "bidirectional"))
    )
    (net (code "60") (name "unconnected-(USB-C-SBU1-PadA8)") (class "Default")
      (node (ref "USB-C") (pin "A8") (pinfunction "SBU1_A8") (pintype "passive"))
    )
    (net (code "61") (name "unconnected-(USB-C-SBU2-PadB8)") (class "Default")
      (node (ref "USB-C") (pin "B8") (pinfunction "SBU2_B8") (pintype "passive"))
    )
    (net (code "62") (name "~{BAT_ALERT}") (class "Default")
      (node (ref "IC1") (pin "4") (pinfunction "P1_3_4") (pintype "bidirectional"))
      (node (ref "R21") (pin "2") (pinfunction "2_2") (pintype "passive"))
      (node (ref "U1") (pin "5") (pinfunction "~{ALRT}_5") (pintype "output"))
    )
  )
)
